# feeder.net
KiCad netlist of a schematic drawn in Altium Designer
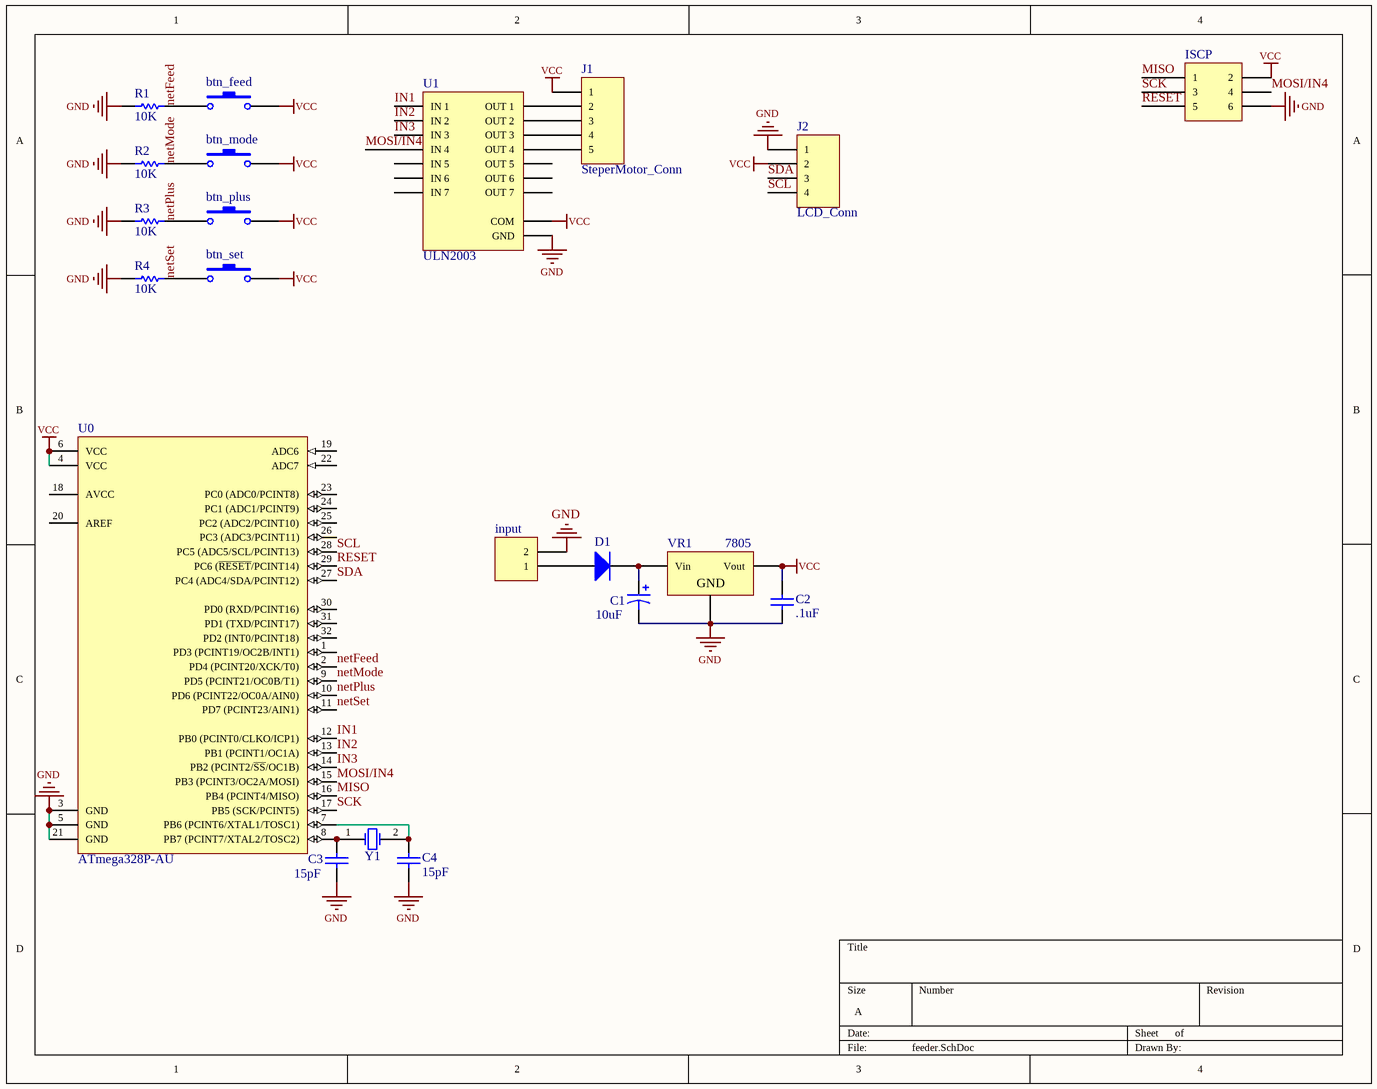
[diagram p0: feeder.SchDoc]

(export (version "E")
  (design (tool "Eeschema 10.0.6"))
  (components
    (comp (ref "btn_feed")
      (value "SW-PB")
      (footprint "BUTTON")
      (description "Switch")
      (fields (field (name "PUBLISHER") "Altium Limited"))
      (libsource (lib "Miscellaneous Devices") (part "SW-PB"))
    )
    (comp (ref "btn_mode")
      (value "SW-PB")
      (footprint "BUTTON")
      (description "Switch")
      (fields (field (name "PUBLISHER") "Altium Limited"))
      (libsource (lib "Miscellaneous Devices") (part "SW-PB"))
    )
    (comp (ref "btn_plus")
      (value "SW-PB")
      (footprint "BUTTON")
      (description "Switch")
      (fields (field (name "PUBLISHER") "Altium Limited"))
      (libsource (lib "Miscellaneous Devices") (part "SW-PB"))
    )
    (comp (ref "btn_set")
      (value "SW-PB")
      (footprint "BUTTON")
      (description "Switch")
      (fields (field (name "PUBLISHER") "Altium Limited"))
      (libsource (lib "Miscellaneous Devices") (part "SW-PB"))
    )
    (comp (ref "C1")
      (value "10uF")
      (footprint "C100_round")
      (description "Polarized Capacitor (Radial)")
      (fields (field (name "Comment") "Cap Pol1") (field (name "PUBLISHER") "Altium Limited"))
      (libsource (lib "Miscellaneous Devices") (part "Cap Pol1"))
    )
    (comp (ref "C2")
      (value ".1uF")
      (footprint "C100_round")
      (description "Capacitor")
      (fields (field (name "Comment") "Cap") (field (name "PUBLISHER") "Altium Limited"))
      (libsource (lib "Miscellaneous Devices") (part "Cap"))
    )
    (comp (ref "C3")
      (value "15pF")
      (footprint "Cap1206_throu")
      (description "Capacitor")
      (fields (field (name "Comment") "Cap") (field (name "PUBLISHER") "Altium Limited"))
      (libsource (lib "Miscellaneous Devices") (part "Cap"))
    )
    (comp (ref "C4")
      (value "15pF")
      (footprint "Cap1206_throu")
      (description "Capacitor")
      (fields (field (name "Comment") "Cap") (field (name "PUBLISHER") "Altium Limited"))
      (libsource (lib "Miscellaneous Devices") (part "Cap"))
    )
    (comp (ref "D1")
      (value "Diode")
      (footprint "Diode_smd_throug")
      (description "Default Diode")
      (fields (field (name "PUBLISHER") "Altium Limited"))
      (libsource (lib "Miscellaneous Devices") (part "Diode"))
    )
    (comp (ref "input")
      (value "POWER IN")
      (footprint "C_120x100")
      (description "Header, 2-Pin")
      (fields (field (name "PUBLISHER") "Altium Limited"))
      (libsource (lib "Miscellaneous Connectors") (part "Header 2"))
    )
    (comp (ref "ISCP")
      (value "Header 3X2")
      (footprint "ISP_6pin_2")
      (description "Header, 3-Pin, Dual row")
      (fields (field (name "PUBLISHER") "Altium Limited"))
      (libsource (lib "Miscellaneous Connectors") (part "Header 3X2"))
    )
    (comp (ref "J1")
      (value "SteperMotor_Conn")
      (footprint "HDR1X5")
      (description "Header, 5-Pin")
      (fields (field (name "PUBLISHER") "Altium Limited"))
      (libsource (lib "Miscellaneous Connectors") (part "Header 5"))
    )
    (comp (ref "J2")
      (value "LCD_Conn")
      (footprint "HDR1X4")
      (description "Header, 4-Pin")
      (fields (field (name "PUBLISHER") "Altium Limited"))
      (libsource (lib "Miscellaneous Connectors") (part "Header 4"))
    )
    (comp (ref "R1")
      (value "10K")
      (footprint "Cap1206_new")
      (description "Resistor")
      (fields (field (name "Comment") "Res1") (field (name "PUBLISHER") "Altium Limited"))
      (libsource (lib "Miscellaneous Devices") (part "Res1"))
    )
    (comp (ref "R2")
      (value "10K")
      (footprint "Cap1206_new")
      (description "Resistor")
      (fields (field (name "Comment") "Res1") (field (name "PUBLISHER") "Altium Limited"))
      (libsource (lib "Miscellaneous Devices") (part "Res1"))
    )
    (comp (ref "R3")
      (value "10K")
      (footprint "Cap1206_new")
      (description "Resistor")
      (fields (field (name "Comment") "Res1") (field (name "PUBLISHER") "Altium Limited"))
      (libsource (lib "Miscellaneous Devices") (part "Res1"))
    )
    (comp (ref "R4")
      (value "10K")
      (footprint "Cap1206_new")
      (description "Resistor")
      (fields (field (name "Comment") "Res1") (field (name "PUBLISHER") "Altium Limited"))
      (libsource (lib "Miscellaneous Devices") (part "Res1"))
    )
    (comp (ref "U0")
      (value "ATmega328P-AU")
      (footprint "TQFP_32_Atmega8a")
      (fields (field (name "PUBLISHER") "Altium Limited"))
      (libsource (lib "Atmel Microcontroller 8-Bit megaAVR") (part "ATmega328P-AU"))
    )
    (comp (ref "U1") (value "ULN2003") (footprint "SOIC16") (libsource (lib "Schlib1") (part "ULN2003")))
    (comp (ref "VR1")
      (value "7805")
      (footprint "SOT-223B")
      (description "Voltage Regulator")
      (fields (field (name "PUBLISHER") "Altium Limited"))
      (libsource (lib "Miscellaneous Devices") (part "Volt Reg"))
    )
    (comp (ref "Y1")
      (value "XTAL")
      (footprint "XTAL-2")
      (description "Crystal Oscillator")
      (fields (field (name "PUBLISHER") "Altium Limited"))
      (libsource (lib "Miscellaneous Devices") (part "XTAL"))
    )
  )
  (nets
    (net (code "1") (name "/IN1") (class "Default")
      (node (ref "U0") (pin "12") (pinfunction "PB0_(PCINT0/CLKO/ICP1)_12") (pintype "bidirectional"))
      (node (ref "U1") (pin "1") (pinfunction "IN_1_1") (pintype "passive"))
    )
    (net (code "2") (name "/IN2") (class "Default")
      (node (ref "U0") (pin "13") (pinfunction "PB1_(PCINT1/OC1A)_13") (pintype "bidirectional"))
      (node (ref "U1") (pin "2") (pinfunction "IN_2_2") (pintype "passive"))
    )
    (net (code "3") (name "/IN3") (class "Default")
      (node (ref "U0") (pin "14") (pinfunction "PB2_(PCINT2/~{SS}/OC1B)_14") (pintype "bidirectional"))
      (node (ref "U1") (pin "3") (pinfunction "IN_3_3") (pintype "passive"))
    )
    (net (code "4") (name "/MISO") (class "Default")
      (node (ref "ISCP") (pin "1") (pinfunction "1_1") (pintype "passive"))
      (node (ref "U0") (pin "16") (pinfunction "PB4_(PCINT4/MISO)_16") (pintype "bidirectional"))
    )
    (net (code "5") (name "/MOSI{slash}IN4") (class "Default")
      (node (ref "ISCP") (pin "4") (pinfunction "4_4") (pintype "passive"))
      (node (ref "U0") (pin "15") (pinfunction "PB3_(PCINT3/OC2A/MOSI)_15") (pintype "bidirectional"))
      (node (ref "U1") (pin "4") (pinfunction "IN_4_4") (pintype "passive"))
    )
    (net (code "6") (name "/RESET") (class "Default")
      (node (ref "ISCP") (pin "5") (pinfunction "5_5") (pintype "passive"))
      (node (ref "U0") (pin "29") (pinfunction "PC6_(~{RESET}/PCINT14)_29") (pintype "bidirectional"))
    )
    (net (code "7") (name "/SCK") (class "Default")
      (node (ref "ISCP") (pin "3") (pinfunction "3_3") (pintype "passive"))
      (node (ref "U0") (pin "17") (pinfunction "PB5_(SCK/PCINT5)_17") (pintype "bidirectional"))
    )
    (net (code "8") (name "/SCL") (class "Default")
      (node (ref "J2") (pin "4") (pinfunction "4_4") (pintype "passive"))
      (node (ref "U0") (pin "28") (pinfunction "PC5_(ADC5/SCL/PCINT13)_28") (pintype "bidirectional"))
    )
    (net (code "9") (name "/SDA") (class "Default")
      (node (ref "J2") (pin "3") (pinfunction "3_3") (pintype "passive"))
      (node (ref "U0") (pin "27") (pinfunction "PC4_(ADC4/SDA/PCINT12)_27") (pintype "bidirectional"))
    )
    (net (code "10") (name "/netFeed") (class "Default")
      (node (ref "R1") (pin "1") (pinfunction "1_1") (pintype "passive"))
      (node (ref "U0") (pin "2") (pinfunction "PD4_(PCINT20/XCK/T0)_2") (pintype "bidirectional"))
      (node (ref "btn_feed") (pin "1") (pinfunction "1_1") (pintype "passive"))
    )
    (net (code "11") (name "/netMode") (class "Default")
      (node (ref "R2") (pin "1") (pinfunction "1_1") (pintype "passive"))
      (node (ref "U0") (pin "9") (pinfunction "PD5_(PCINT21/OC0B/T1)_9") (pintype "bidirectional"))
      (node (ref "btn_mode") (pin "1") (pinfunction "1_1") (pintype "passive"))
    )
    (net (code "12") (name "/netPlus") (class "Default")
      (node (ref "R3") (pin "1") (pinfunction "1_1") (pintype "passive"))
      (node (ref "U0") (pin "10") (pinfunction "PD6_(PCINT22/OC0A/AIN0)_10") (pintype "bidirectional"))
      (node (ref "btn_plus") (pin "1") (pinfunction "1_1") (pintype "passive"))
    )
    (net (code "13") (name "/netSet") (class "Default")
      (node (ref "R4") (pin "1") (pinfunction "1_1") (pintype "passive"))
      (node (ref "U0") (pin "11") (pinfunction "PD7_(PCINT23/AIN1)_11") (pintype "bidirectional"))
      (node (ref "btn_set") (pin "1") (pinfunction "1_1") (pintype "passive"))
    )
    (net (code "14") (name "GND") (class "Default")
      (node (ref "C1") (pin "2") (pinfunction "2_2") (pintype "passive"))
      (node (ref "C2") (pin "2") (pinfunction "2_2") (pintype "passive"))
      (node (ref "C3") (pin "1") (pinfunction "1_1") (pintype "passive"))
      (node (ref "C4") (pin "1") (pinfunction "1_1") (pintype "passive"))
      (node (ref "ISCP") (pin "6") (pinfunction "6_6") (pintype "passive"))
      (node (ref "J2") (pin "1") (pinfunction "1_1") (pintype "passive"))
      (node (ref "R1") (pin "2") (pinfunction "2_2") (pintype "passive"))
      (node (ref "R2") (pin "2") (pinfunction "2_2") (pintype "passive"))
      (node (ref "R3") (pin "2") (pinfunction "2_2") (pintype "passive"))
      (node (ref "R4") (pin "2") (pinfunction "2_2") (pintype "passive"))
      (node (ref "U0") (pin "21") (pinfunction "GND_21") (pintype "power_in"))
      (node (ref "U0") (pin "3") (pinfunction "GND_3") (pintype "power_in"))
      (node (ref "U0") (pin "5") (pinfunction "GND_5") (pintype "power_in"))
      (node (ref "U1") (pin "8") (pinfunction "GND_8") (pintype "passive"))
      (node (ref "VR1") (pin "2") (pinfunction "GND_2") (pintype "passive"))
      (node (ref "input") (pin "2") (pinfunction "2_2") (pintype "passive"))
    )
    (net (code "15") (name "Net-(D1-A)") (class "Default")
      (node (ref "D1") (pin "1") (pinfunction "A_1") (pintype "passive"))
      (node (ref "input") (pin "1") (pinfunction "1_1") (pintype "passive"))
    )
    (net (code "16") (name "Net-(D1-K)") (class "Default")
      (node (ref "C1") (pin "1") (pinfunction "1_1") (pintype "passive"))
      (node (ref "D1") (pin "2") (pinfunction "K_2") (pintype "passive"))
      (node (ref "VR1") (pin "1") (pinfunction "Vin_1") (pintype "passive"))
    )
    (net (code "17") (name "Net-(U0-PB6_(PCINT6{slash}XTAL1{slash}TOSC1))") (class "Default")
      (node (ref "C4") (pin "2") (pinfunction "2_2") (pintype "passive"))
      (node (ref "U0") (pin "7") (pinfunction "PB6_(PCINT6/XTAL1/TOSC1)_7") (pintype "bidirectional"))
      (node (ref "Y1") (pin "2") (pinfunction "OSC2_2") (pintype "passive"))
    )
    (net (code "18") (name "Net-(U0-PB7_(PCINT7{slash}XTAL2{slash}TOSC2))") (class "Default")
      (node (ref "C3") (pin "2") (pinfunction "2_2") (pintype "passive"))
      (node (ref "U0") (pin "8") (pinfunction "PB7_(PCINT7/XTAL2/TOSC2)_8") (pintype "bidirectional"))
      (node (ref "Y1") (pin "1") (pinfunction "OSC1_1") (pintype "passive"))
    )
    (net (code "19") (name "Net-(U1-OUT_1)") (class "Default")
      (node (ref "J1") (pin "2") (pinfunction "2_2") (pintype "passive"))
      (node (ref "U1") (pin "16") (pinfunction "OUT_1_16") (pintype "passive"))
    )
    (net (code "20") (name "Net-(U1-OUT_2)") (class "Default")
      (node (ref "J1") (pin "3") (pinfunction "3_3") (pintype "passive"))
      (node (ref "U1") (pin "15") (pinfunction "OUT_2_15") (pintype "passive"))
    )
    (net (code "21") (name "Net-(U1-OUT_3)") (class "Default")
      (node (ref "J1") (pin "4") (pinfunction "4_4") (pintype "passive"))
      (node (ref "U1") (pin "14") (pinfunction "OUT_3_14") (pintype "passive"))
    )
    (net (code "22") (name "Net-(U1-OUT_4)") (class "Default")
      (node (ref "J1") (pin "5") (pinfunction "5_5") (pintype "passive"))
      (node (ref "U1") (pin "13") (pinfunction "OUT_4_13") (pintype "passive"))
    )
    (net (code "23") (name "VCC") (class "Default")
      (node (ref "C2") (pin "1") (pinfunction "1_1") (pintype "passive"))
      (node (ref "ISCP") (pin "2") (pinfunction "2_2") (pintype "passive"))
      (node (ref "J1") (pin "1") (pinfunction "1_1") (pintype "passive"))
      (node (ref "J2") (pin "2") (pinfunction "2_2") (pintype "passive"))
      (node (ref "U0") (pin "4") (pinfunction "VCC_4") (pintype "power_in"))
      (node (ref "U0") (pin "6") (pinfunction "VCC_6") (pintype "power_in"))
      (node (ref "U1") (pin "9") (pinfunction "COM_9") (pintype "passive"))
      (node (ref "VR1") (pin "3") (pinfunction "Vout_3") (pintype "passive"))
      (node (ref "btn_feed") (pin "2") (pinfunction "2_2") (pintype "passive"))
      (node (ref "btn_mode") (pin "2") (pinfunction "2_2") (pintype "passive"))
      (node (ref "btn_plus") (pin "2") (pinfunction "2_2") (pintype "passive"))
      (node (ref "btn_set") (pin "2") (pinfunction "2_2") (pintype "passive"))
    )
    (net (code "24") (name "unconnected-(U0-ADC6-Pad19)") (class "Default")
      (node (ref "U0") (pin "19") (pinfunction "ADC6_19") (pintype "input"))
    )
    (net (code "25") (name "unconnected-(U0-ADC7-Pad22)") (class "Default")
      (node (ref "U0") (pin "22") (pinfunction "ADC7_22") (pintype "input"))
    )
    (net (code "26") (name "unconnected-(U0-AREF-Pad20)") (class "Default")
      (node (ref "U0") (pin "20") (pinfunction "AREF_20") (pintype "passive"))
    )
    (net (code "27") (name "unconnected-(U0-AVCC-Pad18)") (class "Default")
      (node (ref "U0") (pin "18") (pinfunction "AVCC_18") (pintype "power_in"))
    )
    (net (code "28") (name "unconnected-(U0-PC0_(ADC0{slash}PCINT8)-Pad23)") (class "Default")
      (node (ref "U0") (pin "23") (pinfunction "PC0_(ADC0/PCINT8)_23") (pintype "bidirectional"))
    )
    (net (code "29") (name "unconnected-(U0-PC1_(ADC1{slash}PCINT9)-Pad24)") (class "Default")
      (node (ref "U0") (pin "24") (pinfunction "PC1_(ADC1/PCINT9)_24") (pintype "bidirectional"))
    )
    (net (code "30") (name "unconnected-(U0-PC2_(ADC2{slash}PCINT10)-Pad25)") (class "Default")
      (node (ref "U0") (pin "25") (pinfunction "PC2_(ADC2/PCINT10)_25") (pintype "bidirectional"))
    )
    (net (code "31") (name "unconnected-(U0-PC3_(ADC3{slash}PCINT11)-Pad26)") (class "Default")
      (node (ref "U0") (pin "26") (pinfunction "PC3_(ADC3/PCINT11)_26") (pintype "bidirectional"))
    )
    (net (code "32") (name "unconnected-(U0-PD0_(RXD{slash}PCINT16)-Pad30)") (class "Default")
      (node (ref "U0") (pin "30") (pinfunction "PD0_(RXD/PCINT16)_30") (pintype "bidirectional"))
    )
    (net (code "33") (name "unconnected-(U0-PD1_(TXD{slash}PCINT17)-Pad31)") (class "Default")
      (node (ref "U0") (pin "31") (pinfunction "PD1_(TXD/PCINT17)_31") (pintype "bidirectional"))
    )
    (net (code "34") (name "unconnected-(U0-PD2_(INT0{slash}PCINT18)-Pad32)") (class "Default")
      (node (ref "U0") (pin "32") (pinfunction "PD2_(INT0/PCINT18)_32") (pintype "bidirectional"))
    )
    (net (code "35") (name "unconnected-(U0-PD3_(PCINT19{slash}OC2B{slash}INT1)-Pad1)") (class "Default")
      (node (ref "U0") (pin "1") (pinfunction "PD3_(PCINT19/OC2B/INT1)_1") (pintype "bidirectional"))
    )
    (net (code "36") (name "unconnected-(U1-IN_5-Pad5)") (class "Default")
      (node (ref "U1") (pin "5") (pinfunction "IN_5_5") (pintype "passive"))
    )
    (net (code "37") (name "unconnected-(U1-IN_6-Pad6)") (class "Default")
      (node (ref "U1") (pin "6") (pinfunction "IN_6_6") (pintype "passive"))
    )
    (net (code "38") (name "unconnected-(U1-IN_7-Pad7)") (class "Default")
      (node (ref "U1") (pin "7") (pinfunction "IN_7_7") (pintype "passive"))
    )
    (net (code "39") (name "unconnected-(U1-OUT_5-Pad12)") (class "Default")
      (node (ref "U1") (pin "12") (pinfunction "OUT_5_12") (pintype "passive"))
    )
    (net (code "40") (name "unconnected-(U1-OUT_6-Pad11)") (class "Default")
      (node (ref "U1") (pin "11") (pinfunction "OUT_6_11") (pintype "passive"))
    )
    (net (code "41") (name "unconnected-(U1-OUT_7-Pad10)") (class "Default")
      (node (ref "U1") (pin "10") (pinfunction "OUT_7_10") (pintype "passive"))
    )
  )
)
